# MCU.net
KiCad netlist of a schematic drawn in Altium Designer
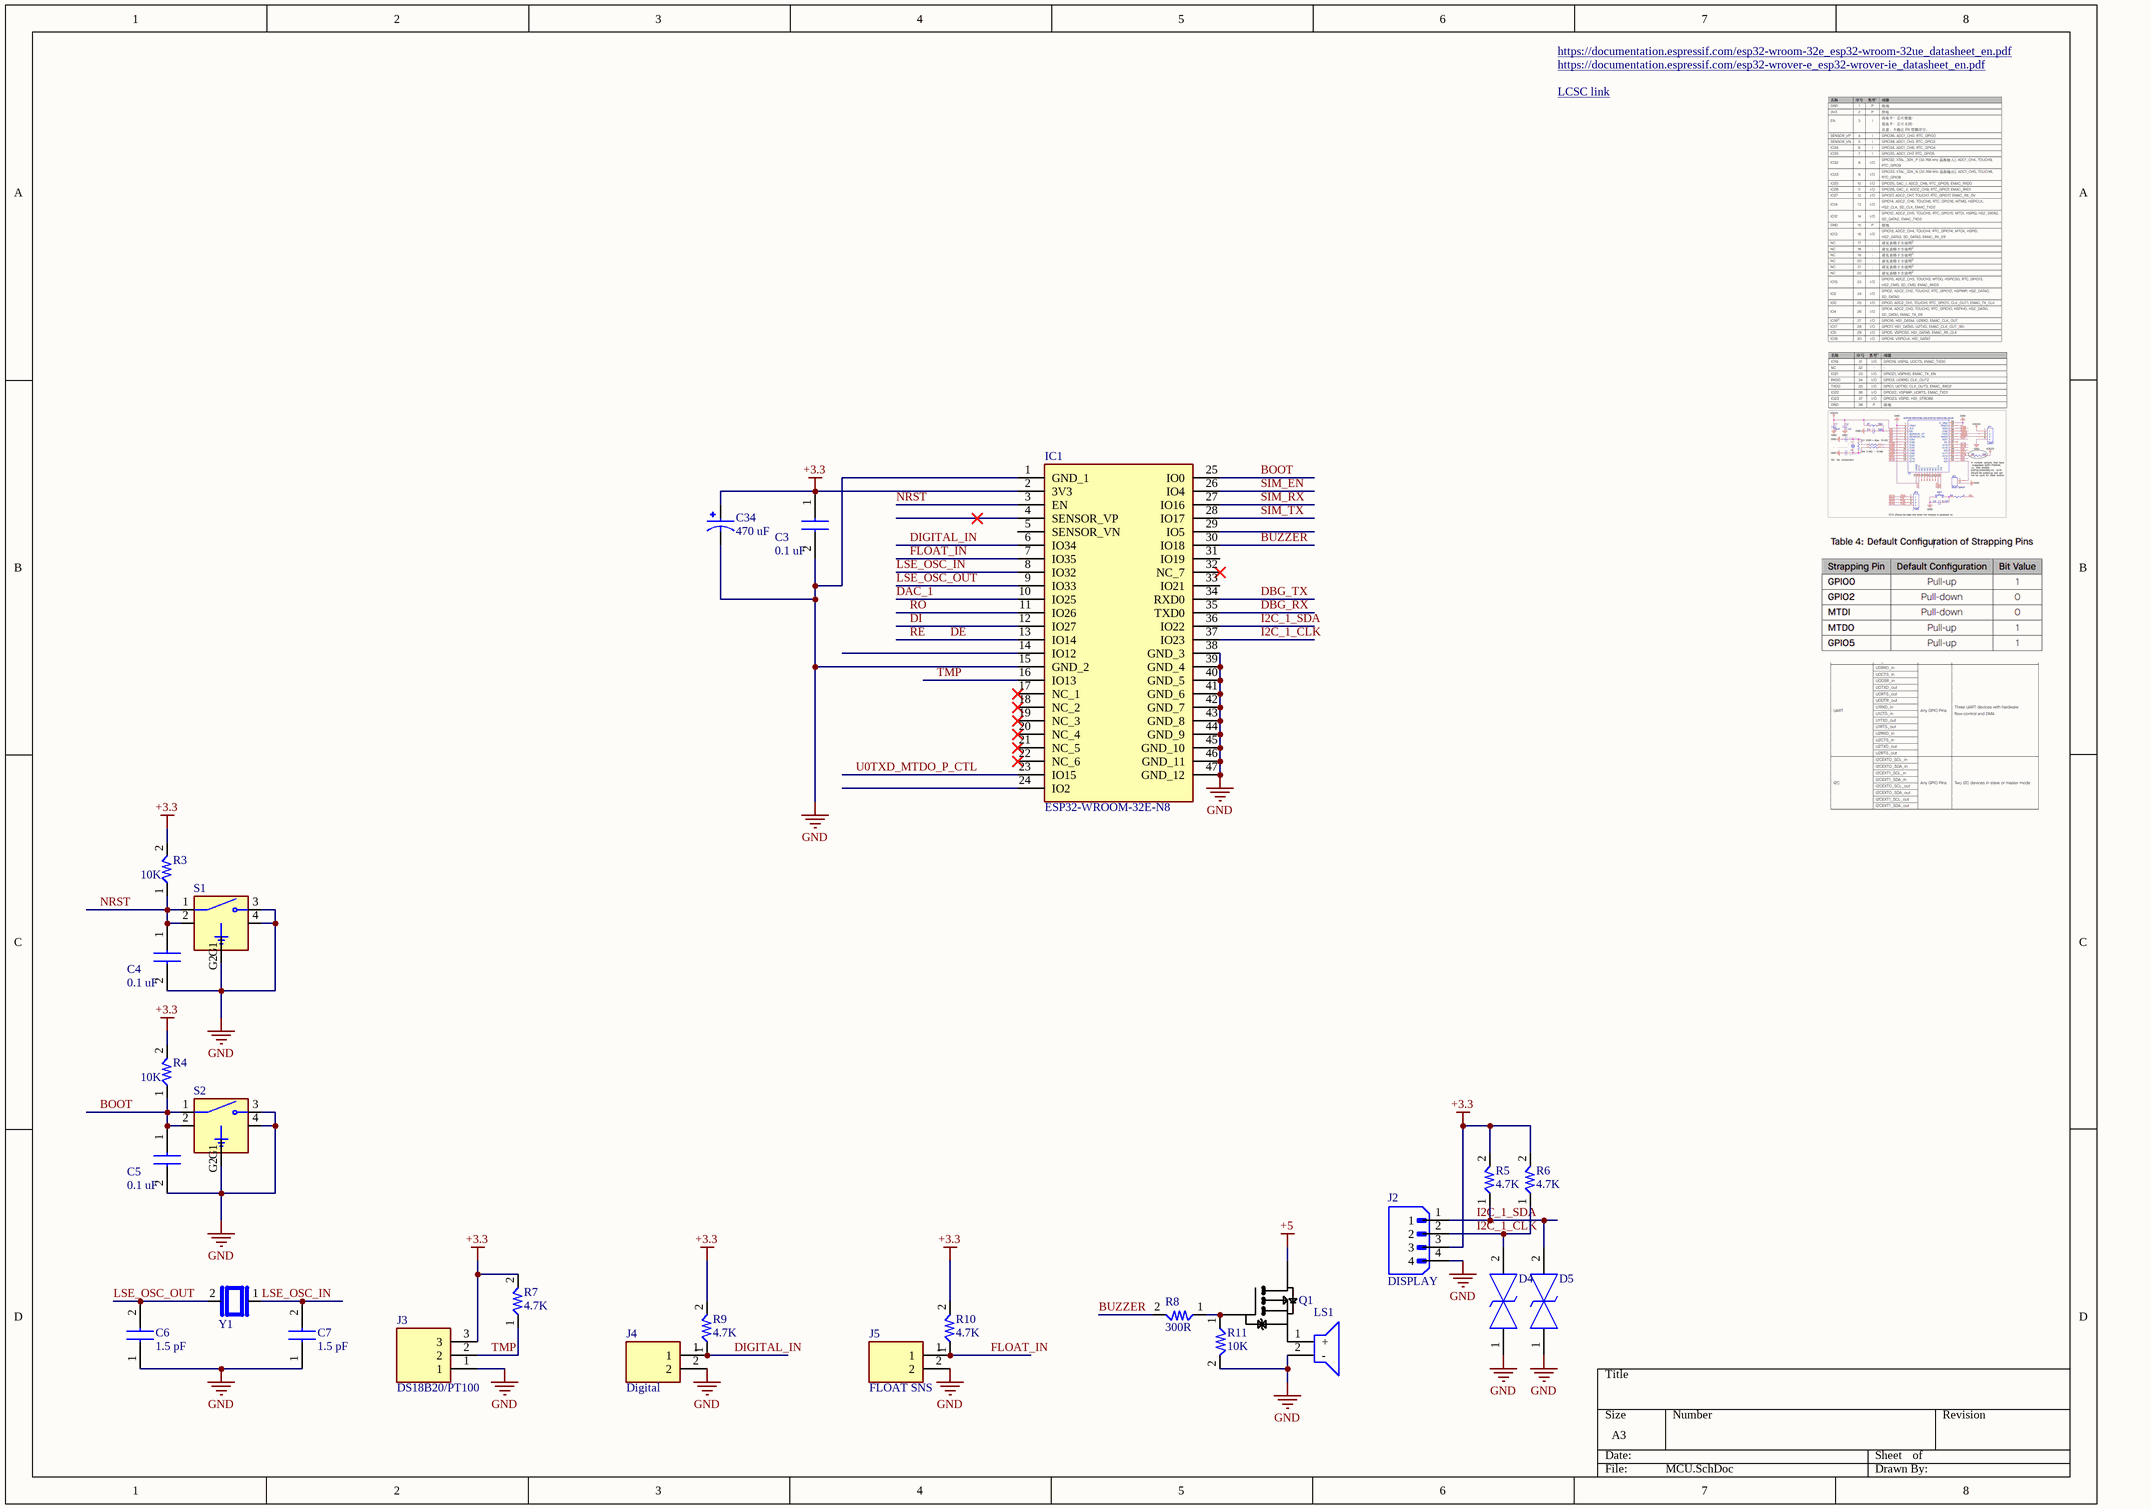
[diagram p0: MCU.SchDoc]

(export (version "E")
  (design (tool "Eeschema 10.0.6"))
  (components
    (comp (ref "C3")
      (value "0.1 uF")
      (footprint "CAP0603")
      (description "Capacitor")
      (fields
        (field (name "MANUFACTURER_PART_NUMBER") "CC0603KRX7R9BB104")
        (field (name "MOUSER PART NUMBER") "603-CC603KRX7R9BB104")
      )
      (libsource (lib "Valve_Controller_Lib") (part "CC0603KRX7R9BB104"))
    )
    (comp (ref "C4")
      (value "0.1 uF")
      (footprint "CAP0603")
      (description "Capacitor")
      (fields
        (field (name "MANUFACTURER_PART_NUMBER") "CC0603KRX7R9BB104")
        (field (name "MOUSER PART NUMBER") "603-CC603KRX7R9BB104")
      )
      (libsource (lib "Valve_Controller_Lib") (part "CC0603KRX7R9BB104"))
    )
    (comp (ref "C5")
      (value "0.1 uF")
      (footprint "CAP0603")
      (description "Capacitor")
      (fields
        (field (name "MANUFACTURER_PART_NUMBER") "CC0603KRX7R9BB104")
        (field (name "MOUSER PART NUMBER") "603-CC603KRX7R9BB104")
      )
      (libsource (lib "Valve_Controller_Lib") (part "CC0603KRX7R9BB104"))
    )
    (comp (ref "C6")
      (value "1.5 pF")
      (footprint "CAP0603")
      (description "Capacitor")
      (fields
        (field (name "MANUFACTURER_PART_NUMBER") "CC0603KRX7R9BB104")
        (field (name "MOUSER PART NUMBER") "603-CC603KRX7R9BB104")
      )
      (libsource (lib "Valve_Controller_Lib") (part "CC0603KRX7R9BB104"))
    )
    (comp (ref "C7")
      (value "1.5 pF")
      (footprint "CAP0603")
      (description "Capacitor")
      (fields
        (field (name "MANUFACTURER_PART_NUMBER") "CC0603KRX7R9BB104")
        (field (name "MOUSER PART NUMBER") "603-CC603KRX7R9BB104")
      )
      (libsource (lib "Valve_Controller_Lib") (part "CC0603KRX7R9BB104"))
    )
    (comp (ref "C34")
      (value "470 uF")
      (footprint "CAPPRD350W60D800H1150")
      (description "220F 25V Aluminum Electrolytic Capacitors Radial, Can 2000 Hrs @ 105C")
      (fields (field (name "MF") "Panasonic") (field (name "MP") "EEUFC1E221"))
      (libsource (lib "EEUFC1E221") (part "EEUFC1E221"))
    )
    (comp (ref "D4")
      (value "DESD3V3Z1BCSF-7")
      (footprint "SamacSys:DESD3V3Z1BCSF7")
      (description "TVS Diode (Bi-directional)")
      (fields (field (name "MOUSER PART NUMBER") "621-DESD3V3Z1BCSF-7"))
      (libsource (lib "*") (part "DESD3V3Z1BCSF-7"))
    )
    (comp (ref "D5")
      (value "DESD3V3Z1BCSF-7")
      (footprint "SamacSys:DESD3V3Z1BCSF7")
      (description "TVS Diode (Bi-directional)")
      (fields (field (name "MOUSER PART NUMBER") "621-DESD3V3Z1BCSF-7"))
      (libsource (lib "*") (part "DESD3V3Z1BCSF-7"))
    )
    (comp (ref "IC1")
      (value "ESP32-WROOM-32E-N8")
      (footprint "SamacSys:ESP32WROOM32EN8")
      (description "Integrated Circuit")
      (fields (field (name "MOUSER PART NUMBER") "356-ESP32WRM32E164PH"))
      (libsource (lib "*") (part "ESP32-WROOM-32E-N8"))
    )
    (comp (ref "J2")
      (value "DISPLAY")
      (footprint "JST_B4B-XH-A(LF)(SN)")
      (description "Connector Header Through Hole 4 position 0.098 (2.50mm)")
      (fields (field (name "MF") "JST Sales") (field (name "MP") "B4B-XH-A(LF)(SN)"))
      (libsource (lib "Valve_Controller_Lib") (part "B4B-XH-A(LF)(SN)"))
    )
    (comp (ref "J3")
      (value "DS18B20/PT100")
      (footprint "SamacSys:2828153")
      (description "Connector")
      (fields
        (field (name "MANUFACTURER_PART_NUMBER") "282815-3")
        (field (name "MOUSER PART NUMBER") "571-282815-3")
      )
      (libsource (lib "*") (part "282815-3"))
    )
    (comp (ref "J4")
      (value "Digital")
      (footprint "SamacSys:SHDRRA2W102P0X508_1X2_1016X1200X850P")
      (description "Connector")
      (fields
        (field (name "MANUFACTURER_PART_NUMBER") "282815-2")
        (field (name "MOUSER PART NUMBER") "571-282815-2")
      )
      (libsource (lib "*") (part "282815-2"))
    )
    (comp (ref "J5")
      (value "FLOAT SNS")
      (footprint "SamacSys:SHDRRA2W102P0X508_1X2_1016X1200X850P")
      (description "Connector")
      (fields
        (field (name "MANUFACTURER_PART_NUMBER") "282815-2")
        (field (name "MOUSER PART NUMBER") "571-282815-2")
      )
      (libsource (lib "*") (part "282815-2"))
    )
    (comp (ref "LS1")
      (value "CMI-1295IC-0585T")
      (footprint "CMI1295IC0585T")
      (description "Loudspeaker or Buzzer")
      (fields (field (name "MOUSER PART NUMBER") "490-CMI-1295IC-0585T"))
      (libsource (lib "Valve_Controller_Lib") (part "CMI-1295IC-0585T"))
    )
    (comp (ref "Q1")
      (value "DMG3415U-7")
      (footprint "SOT96P240X110-3N")
      (description "Integrated Circuit")
      (libsource (lib "Valve_Controller_Lib") (part "DMG3415U-7"))
    )
    (comp (ref "R3")
      (value "10K")
      (footprint "RES0603")
      (description "Resistor")
      (fields (field (name "MANUFACTURER_PART_NUMBER") "0603WAF1001T5E"))
      (libsource (lib "Valve_Controller_Lib") (part "RES"))
    )
    (comp (ref "R4")
      (value "10K")
      (footprint "RES0603")
      (description "Resistor")
      (fields (field (name "MANUFACTURER_PART_NUMBER") "0603WAF1001T5E"))
      (libsource (lib "Valve_Controller_Lib") (part "RES"))
    )
    (comp (ref "R5")
      (value "4.7K")
      (footprint "RES0603")
      (description "Resistor")
      (fields (field (name "MANUFACTURER_PART_NUMBER") "0603WAF1001T5E"))
      (libsource (lib "Valve_Controller_Lib") (part "RES"))
    )
    (comp (ref "R6")
      (value "4.7K")
      (footprint "RES0603")
      (description "Resistor")
      (fields (field (name "MANUFACTURER_PART_NUMBER") "0603WAF1001T5E"))
      (libsource (lib "Valve_Controller_Lib") (part "RES"))
    )
    (comp (ref "R7")
      (value "4.7K")
      (footprint "RES0603")
      (description "Resistor")
      (fields (field (name "MANUFACTURER_PART_NUMBER") "0603WAF1001T5E"))
      (libsource (lib "Valve_Controller_Lib") (part "RES"))
    )
    (comp (ref "R8")
      (value "300R")
      (footprint "RES0603")
      (description "Resistor")
      (fields (field (name "MANUFACTURER_PART_NUMBER") "0603WAF1001T5E"))
      (libsource (lib "Valve_Controller_Lib") (part "RES"))
    )
    (comp (ref "R9")
      (value "4.7K")
      (footprint "RES0603")
      (description "Resistor")
      (fields (field (name "MANUFACTURER_PART_NUMBER") "0603WAF1001T5E"))
      (libsource (lib "Valve_Controller_Lib") (part "RES"))
    )
    (comp (ref "R10")
      (value "4.7K")
      (footprint "RES0603")
      (description "Resistor")
      (fields (field (name "MANUFACTURER_PART_NUMBER") "0603WAF1001T5E"))
      (libsource (lib "Valve_Controller_Lib") (part "RES"))
    )
    (comp (ref "R11")
      (value "10K")
      (footprint "RES0603")
      (description "Resistor")
      (fields (field (name "MANUFACTURER_PART_NUMBER") "0603WAF1001T5E"))
      (libsource (lib "Valve_Controller_Lib") (part "RES"))
    )
    (comp (ref "S1")
      (value "PTS526_SMG15_SMTR2_LFS")
      (footprint "SW_PTS526_SMG15_SMTR2_LFS")
      (description "Tactile Switch SPST-NO Top Actuated Surface Mount")
      (fields (field (name "MP") "PTS526 SMG15 SMTR2 LFS") (field (name "MF") "C&K"))
      (libsource (lib "Valve_Controller_Lib") (part "PTS526_SMG15_SMTR2_LFS"))
    )
    (comp (ref "S2")
      (value "PTS526_SMG15_SMTR2_LFS")
      (footprint "SW_PTS526_SMG15_SMTR2_LFS")
      (description "Tactile Switch SPST-NO Top Actuated Surface Mount")
      (fields (field (name "MP") "PTS526 SMG15 SMTR2 LFS") (field (name "MF") "C&K"))
      (libsource (lib "Valve_Controller_Lib") (part "PTS526_SMG15_SMTR2_LFS"))
    )
    (comp (ref "Y1")
      (value "CM8V-T1A-32.768KHZ-6PF-20PPM-TA-QC")
      (footprint "XTAL_CM8V-T1A-32.768KHZ-6PF-20PPM-TA-QC")
      (description "Tuning Fork Crystal 32.768kHz in SMD 1.2 x 2.0mm package")
      (fields (field (name "MF") "Micro Crystal") (field (name "MP") "CM8V-T1A-32.768kHz-6pF-20PPM-TA-QC"))
      (libsource (lib "Valve_Controller_Lib") (part "CM8V-T1A-32.768KHZ-6PF-20PPM-TA-QC"))
    )
  )
  (nets
    (net (code "1") (name "+3.3") (class "Default")
      (node (ref "C3") (pin "1") (pinfunction "1_1") (pintype "passive"))
      (node (ref "C34") (pin "P") (pinfunction "P_P") (pintype "passive"))
      (node (ref "IC1") (pin "2") (pinfunction "3V3_2") (pintype "passive"))
      (node (ref "J2") (pin "3") (pinfunction "3_3") (pintype "passive"))
      (node (ref "J3") (pin "3") (pinfunction "3_3") (pintype "passive"))
      (node (ref "R10") (pin "2") (pinfunction "2_2") (pintype "passive"))
      (node (ref "R3") (pin "2") (pinfunction "2_2") (pintype "passive"))
      (node (ref "R4") (pin "2") (pinfunction "2_2") (pintype "passive"))
      (node (ref "R5") (pin "2") (pinfunction "2_2") (pintype "passive"))
      (node (ref "R6") (pin "2") (pinfunction "2_2") (pintype "passive"))
      (node (ref "R7") (pin "2") (pinfunction "2_2") (pintype "passive"))
      (node (ref "R9") (pin "2") (pinfunction "2_2") (pintype "passive"))
    )
    (net (code "2") (name "+5") (class "Default")
      (node (ref "Q1") (pin "3") (pinfunction "D_3") (pintype "passive"))
    )
    (net (code "3") (name "/BOOT") (class "Default")
      (node (ref "C5") (pin "1") (pinfunction "1_1") (pintype "passive"))
      (node (ref "IC1") (pin "25") (pinfunction "IO0_25") (pintype "passive"))
      (node (ref "R4") (pin "1") (pinfunction "1_1") (pintype "passive"))
      (node (ref "S2") (pin "1") (pinfunction "COM_1") (pintype "passive"))
      (node (ref "S2") (pin "2") (pinfunction "COM_2") (pintype "passive"))
    )
    (net (code "4") (name "/BUZZER") (class "Default")
      (node (ref "IC1") (pin "30") (pinfunction "IO18_30") (pintype "passive"))
      (node (ref "R8") (pin "2") (pinfunction "2_2") (pintype "passive"))
    )
    (net (code "5") (name "/DAC_1") (class "Default")
      (node (ref "IC1") (pin "10") (pinfunction "IO25_10") (pintype "passive"))
    )
    (net (code "6") (name "/DBG_RX") (class "Default")
      (node (ref "IC1") (pin "35") (pinfunction "TXD0_35") (pintype "passive"))
    )
    (net (code "7") (name "/DBG_TX") (class "Default")
      (node (ref "IC1") (pin "34") (pinfunction "RXD0_34") (pintype "passive"))
    )
    (net (code "8") (name "/DE") (class "Default")
      (node (ref "IC1") (pin "13") (pinfunction "IO14_13") (pintype "passive"))
    )
    (net (code "9") (name "/DI") (class "Default")
      (node (ref "IC1") (pin "12") (pinfunction "IO27_12") (pintype "passive"))
    )
    (net (code "10") (name "/DIGITAL_IN") (class "Default")
      (node (ref "IC1") (pin "6") (pinfunction "IO34_6") (pintype "passive"))
      (node (ref "J4") (pin "1") (pinfunction "1_1") (pintype "passive"))
      (node (ref "R9") (pin "1") (pinfunction "1_1") (pintype "passive"))
    )
    (net (code "11") (name "/FLOAT_IN") (class "Default")
      (node (ref "IC1") (pin "7") (pinfunction "IO35_7") (pintype "passive"))
      (node (ref "J5") (pin "1") (pinfunction "1_1") (pintype "passive"))
      (node (ref "R10") (pin "1") (pinfunction "1_1") (pintype "passive"))
    )
    (net (code "12") (name "/I2C_1_CLK") (class "Default")
      (node (ref "D4") (pin "2") (pinfunction "2_2") (pintype "passive"))
      (node (ref "IC1") (pin "37") (pinfunction "IO23_37") (pintype "passive"))
      (node (ref "J2") (pin "2") (pinfunction "2_2") (pintype "passive"))
      (node (ref "R6") (pin "1") (pinfunction "1_1") (pintype "passive"))
    )
    (net (code "13") (name "/I2C_1_SDA") (class "Default")
      (node (ref "D5") (pin "2") (pinfunction "2_2") (pintype "passive"))
      (node (ref "IC1") (pin "36") (pinfunction "IO22_36") (pintype "passive"))
      (node (ref "J2") (pin "1") (pinfunction "1_1") (pintype "passive"))
      (node (ref "R5") (pin "1") (pinfunction "1_1") (pintype "passive"))
    )
    (net (code "14") (name "/LSE_OSC_IN") (class "Default")
      (node (ref "C7") (pin "2") (pinfunction "2_2") (pintype "passive"))
      (node (ref "IC1") (pin "8") (pinfunction "IO32_8") (pintype "passive"))
      (node (ref "Y1") (pin "1") (pinfunction "1_1") (pintype "passive"))
    )
    (net (code "15") (name "/LSE_OSC_OUT") (class "Default")
      (node (ref "C6") (pin "2") (pinfunction "2_2") (pintype "passive"))
      (node (ref "IC1") (pin "9") (pinfunction "IO33_9") (pintype "passive"))
      (node (ref "Y1") (pin "2") (pinfunction "2_2") (pintype "passive"))
    )
    (net (code "16") (name "/NRST") (class "Default")
      (node (ref "C4") (pin "1") (pinfunction "1_1") (pintype "passive"))
      (node (ref "IC1") (pin "3") (pinfunction "EN_3") (pintype "passive"))
      (node (ref "R3") (pin "1") (pinfunction "1_1") (pintype "passive"))
      (node (ref "S1") (pin "1") (pinfunction "COM_1") (pintype "passive"))
      (node (ref "S1") (pin "2") (pinfunction "COM_2") (pintype "passive"))
    )
    (net (code "17") (name "/RO") (class "Default")
      (node (ref "IC1") (pin "11") (pinfunction "IO26_11") (pintype "passive"))
    )
    (net (code "18") (name "/SIM_EN") (class "Default")
      (node (ref "IC1") (pin "26") (pinfunction "IO4_26") (pintype "passive"))
    )
    (net (code "19") (name "/SIM_RX") (class "Default")
      (node (ref "IC1") (pin "27") (pinfunction "IO16_27") (pintype "passive"))
    )
    (net (code "20") (name "/SIM_TX") (class "Default")
      (node (ref "IC1") (pin "28") (pinfunction "IO17_28") (pintype "passive"))
    )
    (net (code "21") (name "/TMP") (class "Default")
      (node (ref "IC1") (pin "16") (pinfunction "IO13_16") (pintype "passive"))
      (node (ref "J3") (pin "2") (pinfunction "2_2") (pintype "passive"))
      (node (ref "R7") (pin "1") (pinfunction "1_1") (pintype "passive"))
    )
    (net (code "22") (name "/U0TXD_MTDO_P_CTL") (class "Default")
      (node (ref "IC1") (pin "23") (pinfunction "IO15_23") (pintype "passive"))
    )
    (net (code "23") (name "GND") (class "Default")
      (node (ref "C3") (pin "2") (pinfunction "2_2") (pintype "passive"))
      (node (ref "C34") (pin "N") (pinfunction "N_N") (pintype "passive"))
      (node (ref "C4") (pin "2") (pinfunction "2_2") (pintype "passive"))
      (node (ref "C5") (pin "2") (pinfunction "2_2") (pintype "passive"))
      (node (ref "C6") (pin "1") (pinfunction "1_1") (pintype "passive"))
      (node (ref "C7") (pin "1") (pinfunction "1_1") (pintype "passive"))
      (node (ref "D4") (pin "1") (pinfunction "1_1") (pintype "passive"))
      (node (ref "D5") (pin "1") (pinfunction "1_1") (pintype "passive"))
      (node (ref "IC1") (pin "1") (pinfunction "GND_1_1") (pintype "passive"))
      (node (ref "IC1") (pin "15") (pinfunction "GND_2_15") (pintype "passive"))
      (node (ref "IC1") (pin "38") (pinfunction "GND_3_38") (pintype "passive"))
      (node (ref "IC1") (pin "39") (pinfunction "GND_4_39") (pintype "passive"))
      (node (ref "IC1") (pin "40") (pinfunction "GND_5_40") (pintype "passive"))
      (node (ref "IC1") (pin "41") (pinfunction "GND_6_41") (pintype "passive"))
      (node (ref "IC1") (pin "42") (pinfunction "GND_7_42") (pintype "passive"))
      (node (ref "IC1") (pin "43") (pinfunction "GND_8_43") (pintype "passive"))
      (node (ref "IC1") (pin "44") (pinfunction "GND_9_44") (pintype "passive"))
      (node (ref "IC1") (pin "45") (pinfunction "GND_10_45") (pintype "passive"))
      (node (ref "IC1") (pin "46") (pinfunction "GND_11_46") (pintype "passive"))
      (node (ref "IC1") (pin "47") (pinfunction "GND_12_47") (pintype "passive"))
      (node (ref "J2") (pin "4") (pinfunction "4_4") (pintype "passive"))
      (node (ref "J3") (pin "1") (pinfunction "1_1") (pintype "passive"))
      (node (ref "J4") (pin "2") (pinfunction "2_2") (pintype "passive"))
      (node (ref "J5") (pin "2") (pinfunction "2_2") (pintype "passive"))
      (node (ref "LS1") (pin "2") (pinfunction "-_2") (pintype "passive"))
      (node (ref "R11") (pin "2") (pinfunction "2_2") (pintype "passive"))
      (node (ref "S1") (pin "3") (pinfunction "NO_3") (pintype "passive"))
      (node (ref "S1") (pin "4") (pinfunction "NO_4") (pintype "passive"))
      (node (ref "S1") (pin "G2") (pinfunction "GND_G2") (pintype "power_in"))
      (node (ref "S2") (pin "3") (pinfunction "NO_3") (pintype "passive"))
      (node (ref "S2") (pin "4") (pinfunction "NO_4") (pintype "passive"))
      (node (ref "S2") (pin "G2") (pinfunction "GND_G2") (pintype "power_in"))
    )
    (net (code "24") (name "Net-(LS1-+)") (class "Default")
      (node (ref "LS1") (pin "1") (pinfunction "+_1") (pintype "passive"))
      (node (ref "Q1") (pin "2") (pinfunction "S_2") (pintype "passive"))
    )
    (net (code "25") (name "Net-(Q1-G)") (class "Default")
      (node (ref "Q1") (pin "1") (pinfunction "G_1") (pintype "passive"))
      (node (ref "R11") (pin "1") (pinfunction "1_1") (pintype "passive"))
      (node (ref "R8") (pin "1") (pinfunction "1_1") (pintype "passive"))
    )
    (net (code "26") (name "unconnected-(IC1-IO2-Pad24)") (class "Default")
      (node (ref "IC1") (pin "24") (pinfunction "IO2_24") (pintype "passive"))
    )
    (net (code "27") (name "unconnected-(IC1-IO5-Pad29)") (class "Default")
      (node (ref "IC1") (pin "29") (pinfunction "IO5_29") (pintype "passive"))
    )
    (net (code "28") (name "unconnected-(IC1-IO12-Pad14)") (class "Default")
      (node (ref "IC1") (pin "14") (pinfunction "IO12_14") (pintype "passive"))
    )
    (net (code "29") (name "unconnected-(IC1-IO19-Pad31)") (class "Default")
      (node (ref "IC1") (pin "31") (pinfunction "IO19_31") (pintype "passive"))
    )
    (net (code "30") (name "unconnected-(IC1-IO21-Pad33)") (class "Default")
      (node (ref "IC1") (pin "33") (pinfunction "IO21_33") (pintype "passive"))
    )
    (net (code "31") (name "unconnected-(IC1-NC_1-Pad17)") (class "Default")
      (node (ref "IC1") (pin "17") (pinfunction "NC_1_17") (pintype "passive+no_connect"))
    )
    (net (code "32") (name "unconnected-(IC1-NC_2-Pad18)") (class "Default")
      (node (ref "IC1") (pin "18") (pinfunction "NC_2_18") (pintype "passive+no_connect"))
    )
    (net (code "33") (name "unconnected-(IC1-NC_3-Pad19)") (class "Default")
      (node (ref "IC1") (pin "19") (pinfunction "NC_3_19") (pintype "passive+no_connect"))
    )
    (net (code "34") (name "unconnected-(IC1-NC_4-Pad20)") (class "Default")
      (node (ref "IC1") (pin "20") (pinfunction "NC_4_20") (pintype "passive+no_connect"))
    )
    (net (code "35") (name "unconnected-(IC1-NC_5-Pad21)") (class "Default")
      (node (ref "IC1") (pin "21") (pinfunction "NC_5_21") (pintype "passive+no_connect"))
    )
    (net (code "36") (name "unconnected-(IC1-NC_6-Pad22)") (class "Default")
      (node (ref "IC1") (pin "22") (pinfunction "NC_6_22") (pintype "passive+no_connect"))
    )
    (net (code "37") (name "unconnected-(IC1-NC_7-Pad32)") (class "Default")
      (node (ref "IC1") (pin "32") (pinfunction "NC_7_32") (pintype "passive+no_connect"))
    )
    (net (code "38") (name "unconnected-(IC1-SENSOR_VN-Pad5)") (class "Default")
      (node (ref "IC1") (pin "5") (pinfunction "SENSOR_VN_5") (pintype "passive"))
    )
    (net (code "39") (name "unconnected-(IC1-SENSOR_VP-Pad4)") (class "Default")
      (node (ref "IC1") (pin "4") (pinfunction "SENSOR_VP_4") (pintype "passive"))
    )
    (net (code "40") (name "unconnected-(S1-GND-PadG1)") (class "Default")
      (node (ref "S1") (pin "G1") (pinfunction "GND_G1") (pintype "power_in"))
    )
    (net (code "41") (name "unconnected-(S2-GND-PadG1)") (class "Default")
      (node (ref "S2") (pin "G1") (pinfunction "GND_G1") (pintype "power_in"))
    )
  )
)
